# master1.net
KiCad netlist of a schematic drawn in EAGLE
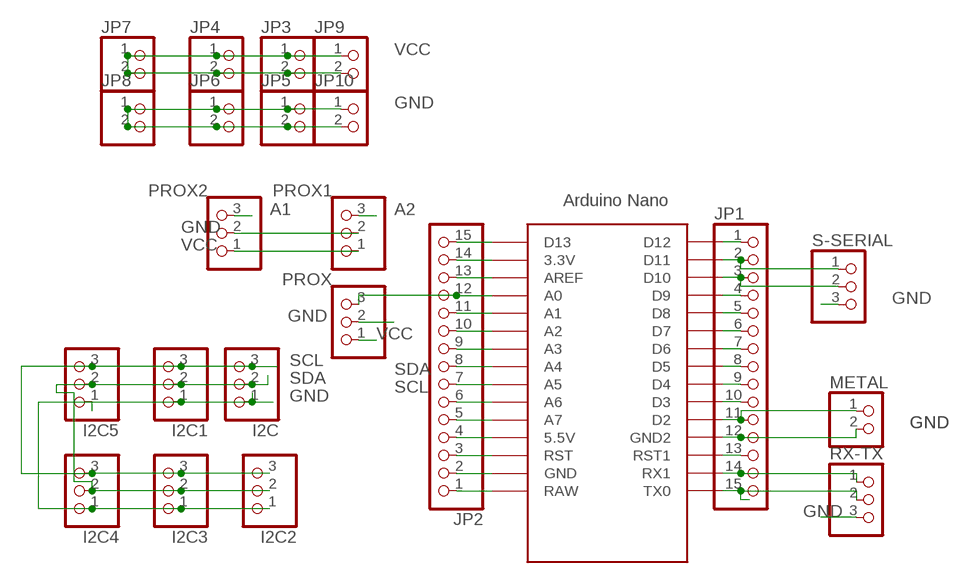
[diagram p0: schematic, sheet 1]

(export (version "E")
  (design (tool "Eeschema 10.0.6"))
  (components
    (comp (ref "I2C")
      (value "PINHD-3_DATA")
      (footprint "eagle-import:1X03_DATA")
      (libsource (lib "eagle-import") (part "PINHD-3_DATA"))
    )
    (comp (ref "I2C1")
      (value "PINHD-3_DATA")
      (footprint "eagle-import:1X03_DATA")
      (libsource (lib "eagle-import") (part "PINHD-3_DATA"))
    )
    (comp (ref "I2C2")
      (value "PINHD-3_DATA")
      (footprint "eagle-import:1X03_DATA")
      (libsource (lib "eagle-import") (part "PINHD-3_DATA"))
    )
    (comp (ref "I2C3")
      (value "PINHD-3_DATA")
      (footprint "eagle-import:1X03_DATA")
      (libsource (lib "eagle-import") (part "PINHD-3_DATA"))
    )
    (comp (ref "I2C4")
      (value "PINHD-3_DATA")
      (footprint "eagle-import:1X03_DATA")
      (libsource (lib "eagle-import") (part "PINHD-3_DATA"))
    )
    (comp (ref "I2C5")
      (value "PINHD-3_DATA")
      (footprint "eagle-import:1X03_DATA")
      (libsource (lib "eagle-import") (part "PINHD-3_DATA"))
    )
    (comp (ref "JP1")
      (value "PINHD-1X15")
      (footprint "eagle-import:1X15")
      (libsource (lib "eagle-import") (part "PINHD-1X15"))
    )
    (comp (ref "JP2")
      (value "PINHD-1X15")
      (footprint "eagle-import:1X15")
      (libsource (lib "eagle-import") (part "PINHD-1X15"))
    )
    (comp (ref "JP3")
      (value "PINHD-1X2")
      (footprint "eagle-import:1X02")
      (libsource (lib "eagle-import") (part "PINHD-1X2"))
    )
    (comp (ref "JP4")
      (value "PINHD-1X2")
      (footprint "eagle-import:1X02")
      (libsource (lib "eagle-import") (part "PINHD-1X2"))
    )
    (comp (ref "JP5")
      (value "PINHD-1X2")
      (footprint "eagle-import:1X02")
      (libsource (lib "eagle-import") (part "PINHD-1X2"))
    )
    (comp (ref "JP6")
      (value "PINHD-1X2")
      (footprint "eagle-import:1X02")
      (libsource (lib "eagle-import") (part "PINHD-1X2"))
    )
    (comp (ref "JP7")
      (value "PINHD-1X2")
      (footprint "eagle-import:1X02")
      (libsource (lib "eagle-import") (part "PINHD-1X2"))
    )
    (comp (ref "JP8")
      (value "PINHD-1X2")
      (footprint "eagle-import:1X02")
      (libsource (lib "eagle-import") (part "PINHD-1X2"))
    )
    (comp (ref "JP9")
      (value "PINHD-1X2")
      (footprint "eagle-import:1X02")
      (libsource (lib "eagle-import") (part "PINHD-1X2"))
    )
    (comp (ref "JP10")
      (value "PINHD-1X2")
      (footprint "eagle-import:1X02")
      (libsource (lib "eagle-import") (part "PINHD-1X2"))
    )
    (comp (ref "METAL")
      (value "PINHD-2_DATA")
      (footprint "eagle-import:1X02_DATA")
      (libsource (lib "eagle-import") (part "PINHD-2_DATA"))
    )
    (comp (ref "PROX")
      (value "PINHD-3_DATA")
      (footprint "eagle-import:1X03_DATA")
      (libsource (lib "eagle-import") (part "PINHD-3_DATA"))
    )
    (comp (ref "PROX1")
      (value "PINHD-3_DATA")
      (footprint "eagle-import:1X03_DATA")
      (libsource (lib "eagle-import") (part "PINHD-3_DATA"))
    )
    (comp (ref "PROX2")
      (value "PINHD-3_DATA")
      (footprint "eagle-import:1X03_DATA")
      (libsource (lib "eagle-import") (part "PINHD-3_DATA"))
    )
    (comp (ref "RX-TX")
      (value "PINHD-3_DATA")
      (footprint "eagle-import:1X03_DATA")
      (libsource (lib "eagle-import") (part "PINHD-3_DATA"))
    )
    (comp (ref "S-SERIAL")
      (value "PINHD-3_DATA")
      (footprint "eagle-import:1X03_DATA")
      (libsource (lib "eagle-import") (part "PINHD-3_DATA"))
    )
    (comp (ref "U$1")
      (value "ARDUINO_NANO")
      (footprint "eagle-import:NANO")
      (libsource (lib "eagle-import") (part "ARDUINO_NANO"))
    )
  )
  (nets
    (net (code "1") (name "/A1") (class "Default")
      (node (ref "PROX2") (pin "3") (pinfunction "3_3") (pintype "passive"))
    )
    (net (code "2") (name "/A2") (class "Default")
      (node (ref "PROX1") (pin "3") (pinfunction "3_3") (pintype "passive"))
    )
    (net (code "3") (name "/GND") (class "Default")
      (node (ref "I2C") (pin "1") (pinfunction "1_1") (pintype "passive"))
      (node (ref "I2C1") (pin "1") (pinfunction "1_1") (pintype "passive"))
      (node (ref "I2C2") (pin "1") (pinfunction "1_1") (pintype "passive"))
      (node (ref "I2C3") (pin "1") (pinfunction "1_1") (pintype "passive"))
      (node (ref "I2C4") (pin "1") (pinfunction "1_1") (pintype "passive"))
      (node (ref "I2C5") (pin "1") (pinfunction "1_1") (pintype "passive"))
      (node (ref "JP1") (pin "12") (pinfunction "12_12") (pintype "passive"))
      (node (ref "JP10") (pin "1") (pinfunction "1_1") (pintype "passive"))
      (node (ref "JP10") (pin "2") (pinfunction "2_2") (pintype "passive"))
      (node (ref "JP5") (pin "1") (pinfunction "1_1") (pintype "passive"))
      (node (ref "JP5") (pin "2") (pinfunction "2_2") (pintype "passive"))
      (node (ref "JP6") (pin "1") (pinfunction "1_1") (pintype "passive"))
      (node (ref "JP6") (pin "2") (pinfunction "2_2") (pintype "passive"))
      (node (ref "JP8") (pin "1") (pinfunction "1_1") (pintype "passive"))
      (node (ref "JP8") (pin "2") (pinfunction "2_2") (pintype "passive"))
      (node (ref "METAL") (pin "2") (pinfunction "2_2") (pintype "passive"))
      (node (ref "PROX") (pin "2") (pinfunction "2_2") (pintype "passive"))
      (node (ref "PROX1") (pin "2") (pinfunction "2_2") (pintype "passive"))
      (node (ref "PROX2") (pin "2") (pinfunction "2_2") (pintype "passive"))
      (node (ref "RX-TX") (pin "3") (pinfunction "3_3") (pintype "passive"))
      (node (ref "S-SERIAL") (pin "3") (pinfunction "3_3") (pintype "passive"))
      (node (ref "U$1") (pin "GND1") (pinfunction "GND2_GND1") (pintype "bidirectional"))
    )
    (net (code "4") (name "/SCL") (class "Default")
      (node (ref "I2C") (pin "3") (pinfunction "3_3") (pintype "passive"))
      (node (ref "I2C1") (pin "3") (pinfunction "3_3") (pintype "passive"))
      (node (ref "I2C2") (pin "3") (pinfunction "3_3") (pintype "passive"))
      (node (ref "I2C3") (pin "3") (pinfunction "3_3") (pintype "passive"))
      (node (ref "I2C4") (pin "3") (pinfunction "3_3") (pintype "passive"))
      (node (ref "I2C5") (pin "3") (pinfunction "3_3") (pintype "passive"))
      (node (ref "JP2") (pin "7") (pinfunction "7_7") (pintype "passive"))
      (node (ref "U$1") (pin "A5") (pinfunction "A5_A5") (pintype "bidirectional"))
    )
    (net (code "5") (name "/SDA") (class "Default")
      (node (ref "I2C") (pin "2") (pinfunction "2_2") (pintype "passive"))
      (node (ref "I2C1") (pin "2") (pinfunction "2_2") (pintype "passive"))
      (node (ref "I2C2") (pin "2") (pinfunction "2_2") (pintype "passive"))
      (node (ref "I2C3") (pin "2") (pinfunction "2_2") (pintype "passive"))
      (node (ref "I2C4") (pin "2") (pinfunction "2_2") (pintype "passive"))
      (node (ref "I2C5") (pin "2") (pinfunction "2_2") (pintype "passive"))
      (node (ref "JP2") (pin "8") (pinfunction "8_8") (pintype "passive"))
      (node (ref "U$1") (pin "A4") (pinfunction "A4_A4") (pintype "bidirectional"))
    )
    (net (code "6") (name "/VCC") (class "Default")
      (node (ref "JP3") (pin "1") (pinfunction "1_1") (pintype "passive"))
      (node (ref "JP3") (pin "2") (pinfunction "2_2") (pintype "passive"))
      (node (ref "JP4") (pin "1") (pinfunction "1_1") (pintype "passive"))
      (node (ref "JP4") (pin "2") (pinfunction "2_2") (pintype "passive"))
      (node (ref "JP7") (pin "1") (pinfunction "1_1") (pintype "passive"))
      (node (ref "JP7") (pin "2") (pinfunction "2_2") (pintype "passive"))
      (node (ref "JP9") (pin "1") (pinfunction "1_1") (pintype "passive"))
      (node (ref "JP9") (pin "2") (pinfunction "2_2") (pintype "passive"))
      (node (ref "PROX") (pin "1") (pinfunction "1_1") (pintype "passive"))
      (node (ref "PROX1") (pin "1") (pinfunction "1_1") (pintype "passive"))
      (node (ref "PROX2") (pin "1") (pinfunction "1_1") (pintype "passive"))
    )
    (net (code "7") (name "Net-(JP1-Pad1)") (class "Default")
      (node (ref "JP1") (pin "1") (pinfunction "1_1") (pintype "passive"))
      (node (ref "U$1") (pin "D12") (pinfunction "D12_D12") (pintype "bidirectional"))
    )
    (net (code "8") (name "Net-(JP1-Pad2)") (class "Default")
      (node (ref "JP1") (pin "2") (pinfunction "2_2") (pintype "passive"))
      (node (ref "S-SERIAL") (pin "1") (pinfunction "1_1") (pintype "passive"))
      (node (ref "U$1") (pin "D11") (pinfunction "D11_D11") (pintype "bidirectional"))
    )
    (net (code "9") (name "Net-(JP1-Pad3)") (class "Default")
      (node (ref "JP1") (pin "3") (pinfunction "3_3") (pintype "passive"))
      (node (ref "S-SERIAL") (pin "2") (pinfunction "2_2") (pintype "passive"))
      (node (ref "U$1") (pin "D10") (pinfunction "D10_D10") (pintype "bidirectional"))
    )
    (net (code "10") (name "Net-(JP1-Pad4)") (class "Default")
      (node (ref "JP1") (pin "4") (pinfunction "4_4") (pintype "passive"))
      (node (ref "U$1") (pin "D9") (pinfunction "D9_D9") (pintype "bidirectional"))
    )
    (net (code "11") (name "Net-(JP1-Pad5)") (class "Default")
      (node (ref "JP1") (pin "5") (pinfunction "5_5") (pintype "passive"))
      (node (ref "U$1") (pin "D8") (pinfunction "D8_D8") (pintype "bidirectional"))
    )
    (net (code "12") (name "Net-(JP1-Pad6)") (class "Default")
      (node (ref "JP1") (pin "6") (pinfunction "6_6") (pintype "passive"))
      (node (ref "U$1") (pin "D7") (pinfunction "D7_D7") (pintype "bidirectional"))
    )
    (net (code "13") (name "Net-(JP1-Pad7)") (class "Default")
      (node (ref "JP1") (pin "7") (pinfunction "7_7") (pintype "passive"))
      (node (ref "U$1") (pin "D6") (pinfunction "D6_D6") (pintype "bidirectional"))
    )
    (net (code "14") (name "Net-(JP1-Pad8)") (class "Default")
      (node (ref "JP1") (pin "8") (pinfunction "8_8") (pintype "passive"))
      (node (ref "U$1") (pin "D5") (pinfunction "D5_D5") (pintype "bidirectional"))
    )
    (net (code "15") (name "Net-(JP1-Pad9)") (class "Default")
      (node (ref "JP1") (pin "9") (pinfunction "9_9") (pintype "passive"))
      (node (ref "U$1") (pin "D4") (pinfunction "D4_D4") (pintype "bidirectional"))
    )
    (net (code "16") (name "Net-(JP1-Pad10)") (class "Default")
      (node (ref "JP1") (pin "10") (pinfunction "10_10") (pintype "passive"))
      (node (ref "U$1") (pin "D3") (pinfunction "D3_D3") (pintype "bidirectional"))
    )
    (net (code "17") (name "Net-(JP1-Pad11)") (class "Default")
      (node (ref "JP1") (pin "11") (pinfunction "11_11") (pintype "passive"))
      (node (ref "METAL") (pin "1") (pinfunction "1_1") (pintype "passive"))
      (node (ref "U$1") (pin "D2") (pinfunction "D2_D2") (pintype "bidirectional"))
    )
    (net (code "18") (name "Net-(JP1-Pad13)") (class "Default")
      (node (ref "JP1") (pin "13") (pinfunction "13_13") (pintype "passive"))
      (node (ref "U$1") (pin "RST1") (pinfunction "RST1_RST1") (pintype "bidirectional"))
    )
    (net (code "19") (name "Net-(JP1-Pad14)") (class "Default")
      (node (ref "JP1") (pin "14") (pinfunction "14_14") (pintype "passive"))
      (node (ref "RX-TX") (pin "1") (pinfunction "1_1") (pintype "passive"))
      (node (ref "U$1") (pin "RX1") (pinfunction "RX1_RX1") (pintype "bidirectional"))
    )
    (net (code "20") (name "Net-(JP1-Pad15)") (class "Default")
      (node (ref "JP1") (pin "15") (pinfunction "15_15") (pintype "passive"))
      (node (ref "RX-TX") (pin "2") (pinfunction "2_2") (pintype "passive"))
      (node (ref "U$1") (pin "TX0") (pinfunction "TX0_TX0") (pintype "bidirectional"))
    )
    (net (code "21") (name "Net-(JP2-Pad1)") (class "Default")
      (node (ref "JP2") (pin "1") (pinfunction "1_1") (pintype "passive"))
      (node (ref "U$1") (pin "RAW") (pinfunction "RAW_RAW") (pintype "bidirectional"))
    )
    (net (code "22") (name "Net-(JP2-Pad2)") (class "Default")
      (node (ref "JP2") (pin "2") (pinfunction "2_2") (pintype "passive"))
      (node (ref "U$1") (pin "GND") (pinfunction "GND_GND") (pintype "bidirectional"))
    )
    (net (code "23") (name "Net-(JP2-Pad3)") (class "Default")
      (node (ref "JP2") (pin "3") (pinfunction "3_3") (pintype "passive"))
      (node (ref "U$1") (pin "RST") (pinfunction "RST_RST") (pintype "bidirectional"))
    )
    (net (code "24") (name "Net-(JP2-Pad5)") (class "Default")
      (node (ref "JP2") (pin "5") (pinfunction "5_5") (pintype "passive"))
      (node (ref "U$1") (pin "A7") (pinfunction "A7_A7") (pintype "bidirectional"))
    )
    (net (code "25") (name "Net-(JP2-Pad6)") (class "Default")
      (node (ref "JP2") (pin "6") (pinfunction "6_6") (pintype "passive"))
      (node (ref "U$1") (pin "A6") (pinfunction "A6_A6") (pintype "bidirectional"))
    )
    (net (code "26") (name "Net-(JP2-Pad9)") (class "Default")
      (node (ref "JP2") (pin "9") (pinfunction "9_9") (pintype "passive"))
      (node (ref "U$1") (pin "A3") (pinfunction "A3_A3") (pintype "bidirectional"))
    )
    (net (code "27") (name "Net-(JP2-Pad10)") (class "Default")
      (node (ref "JP2") (pin "10") (pinfunction "10_10") (pintype "passive"))
      (node (ref "U$1") (pin "A2") (pinfunction "A2_A2") (pintype "bidirectional"))
    )
    (net (code "28") (name "Net-(JP2-Pad11)") (class "Default")
      (node (ref "JP2") (pin "11") (pinfunction "11_11") (pintype "passive"))
      (node (ref "U$1") (pin "A1") (pinfunction "A1_A1") (pintype "bidirectional"))
    )
    (net (code "29") (name "Net-(JP2-Pad12)") (class "Default")
      (node (ref "JP2") (pin "12") (pinfunction "12_12") (pintype "passive"))
      (node (ref "PROX") (pin "3") (pinfunction "3_3") (pintype "passive"))
      (node (ref "U$1") (pin "A0") (pinfunction "A0_A0") (pintype "bidirectional"))
    )
    (net (code "30") (name "Net-(JP2-Pad13)") (class "Default")
      (node (ref "JP2") (pin "13") (pinfunction "13_13") (pintype "passive"))
      (node (ref "U$1") (pin "AREF") (pinfunction "AREF_AREF") (pintype "bidirectional"))
    )
    (net (code "31") (name "Net-(JP2-Pad14)") (class "Default")
      (node (ref "JP2") (pin "14") (pinfunction "14_14") (pintype "passive"))
      (node (ref "U$1") (pin "3.3V") (pinfunction "3.3V_3.3V") (pintype "bidirectional"))
    )
    (net (code "32") (name "Net-(JP2-Pad15)") (class "Default")
      (node (ref "JP2") (pin "15") (pinfunction "15_15") (pintype "passive"))
      (node (ref "U$1") (pin "D13") (pinfunction "D13_D13") (pintype "bidirectional"))
    )
    (net (code "33") (name "Net-(U$1-5.5V)") (class "Default")
      (node (ref "JP2") (pin "4") (pinfunction "4_4") (pintype "passive"))
      (node (ref "U$1") (pin "5V") (pinfunction "5.5V_5V") (pintype "bidirectional"))
    )
  )
)
